# OpAmpNorton.net
KiCad netlist of a schematic drawn in Altium Designer
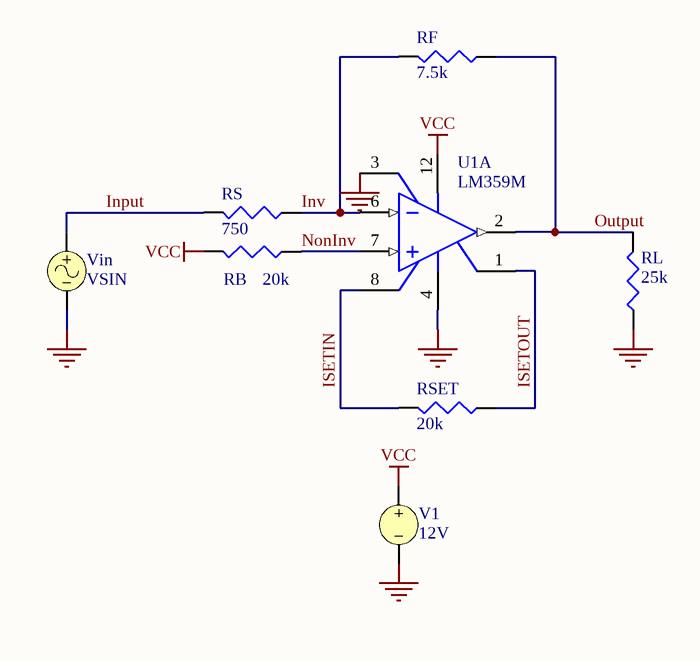
[diagram p0: OpAmpNorton.schdoc]

(export (version "E")
  (design (tool "Eeschema 10.0.6"))
  (components
    (comp (ref "RB")
      (value "20k")
      (description "Resistor")
      (fields (field (name "Comment") "10k"))
      (libsource (lib "*") (part "RES"))
    )
    (comp (ref "RF")
      (value "7.5k")
      (description "Resistor")
      (fields (field (name "Comment") "100k"))
      (libsource (lib "*") (part "RES"))
    )
    (comp (ref "RL") (value "25k") (description "Resistor") (libsource (lib "") (part "RES_1")))
    (comp (ref "RS")
      (value "750")
      (description "Resistor")
      (fields (field (name "Comment") "10k"))
      (libsource (lib "*") (part "RES"))
    )
    (comp (ref "RSET")
      (value "20k")
      (description "Resistor")
      (fields (field (name "Comment") "25k"))
      (libsource (lib "*") (part "RES"))
    )
    (comp (ref "U1")
      (value "LM359M")
      (footprint "M14A_N")
      (description "Dual, High Speed, Programmable, Current Mode (Norton) Amplifiers")
      (fields
        (field (name "MANUFACTURER") "National Semiconductor")
        (field (name "DIGIKEYPARTNUMBER") "LM359M-ND")
        (field (name "PUBLISHER") "Altium Limited")
      )
      (libsource (lib "NSC Amplifier with SIM models") (part "LM359M"))
    )
    (comp (ref "V1") (value "12V") (description "Voltage Source") (libsource (lib "*") (part "VSRC")))
    (comp (ref "Vin")
      (value "VSIN")
      (description "Sinusoidal Voltage Source")
      (libsource (lib "*") (part "VSIN"))
    )
  )
  (nets
    (net (code "1") (name "/ISETIN") (class "Default")
      (node (ref "RSET") (pin "1") (pinfunction "TOP_1") (pintype "passive"))
      (node (ref "U1") (pin "8") (pinfunction "ISET(IN)_8") (pintype "passive"))
    )
    (net (code "2") (name "/ISETOUT") (class "Default")
      (node (ref "RSET") (pin "2") (pinfunction "BOT_2") (pintype "passive"))
      (node (ref "U1") (pin "1") (pinfunction "ISET(OUT)_1") (pintype "passive"))
    )
    (net (code "3") (name "/Input") (class "Default")
      (node (ref "RS") (pin "1") (pinfunction "TOP_1") (pintype "passive"))
      (node (ref "Vin") (pin "1") (pinfunction "1_1") (pintype "passive"))
    )
    (net (code "4") (name "/Inv") (class "Default")
      (node (ref "RF") (pin "1") (pinfunction "TOP_1") (pintype "passive"))
      (node (ref "RS") (pin "2") (pinfunction "BOT_2") (pintype "passive"))
      (node (ref "U1") (pin "6") (pinfunction "INA-_6") (pintype "input"))
    )
    (net (code "5") (name "/NonInv") (class "Default")
      (node (ref "RB") (pin "2") (pinfunction "BOT_2") (pintype "passive"))
      (node (ref "U1") (pin "7") (pinfunction "INA+_7") (pintype "input"))
    )
    (net (code "6") (name "/Output") (class "Default")
      (node (ref "RF") (pin "2") (pinfunction "BOT_2") (pintype "passive"))
      (node (ref "RL") (pin "1") (pinfunction "TOP_1") (pintype "passive"))
      (node (ref "U1") (pin "2") (pinfunction "OUTA_2") (pintype "output"))
    )
    (net (code "7") (name "GND") (class "Default")
      (node (ref "RL") (pin "2") (pinfunction "BOT_2") (pintype "passive"))
      (node (ref "U1") (pin "3") (pinfunction "COMPA_3") (pintype "passive"))
      (node (ref "U1") (pin "4") (pinfunction "GNDA_4") (pintype "power_in"))
      (node (ref "V1") (pin "2") (pinfunction "2_2") (pintype "passive"))
      (node (ref "Vin") (pin "2") (pinfunction "2_2") (pintype "passive"))
    )
    (net (code "8") (name "VCC") (class "Default")
      (node (ref "RB") (pin "1") (pinfunction "TOP_1") (pintype "passive"))
      (node (ref "U1") (pin "12") (pinfunction "V+_12") (pintype "power_in"))
      (node (ref "V1") (pin "1") (pinfunction "1_1") (pintype "passive"))
    )
  )
)
